# Switching_Regulator_LV_Board.net
KiCad netlist of a schematic drawn in Altium Designer
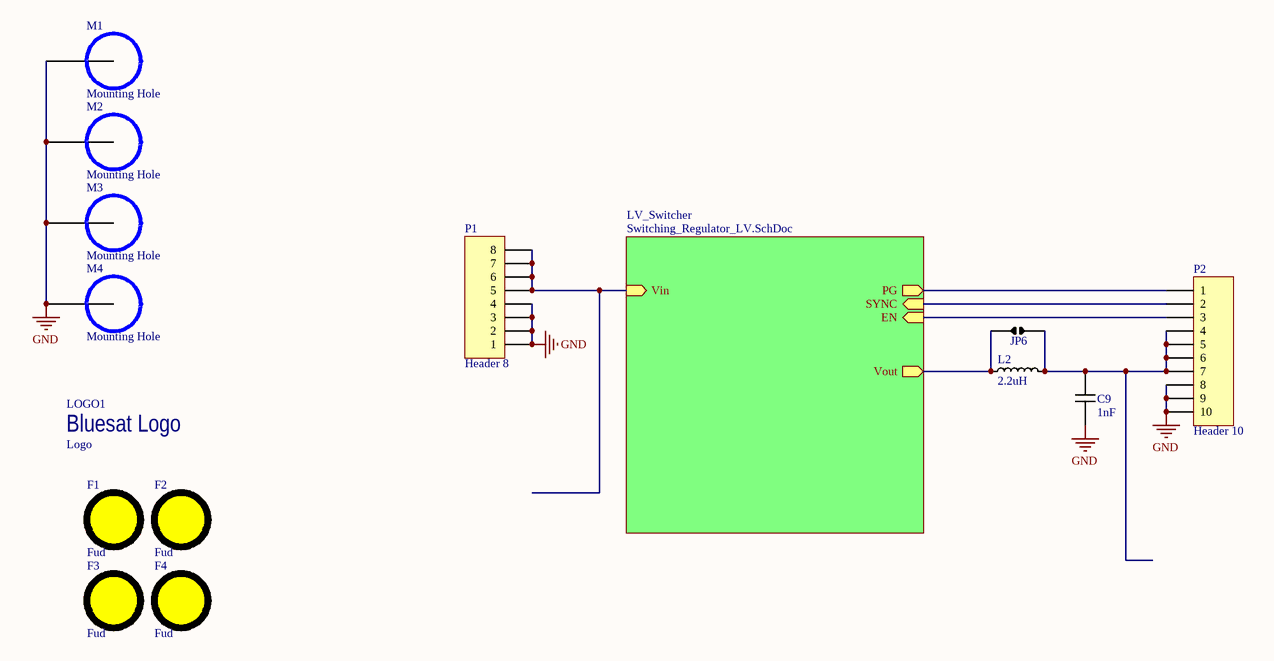
[diagram p0: Switching_Regulator_LV_Board.SchDoc]

(export (version "E")
  (design (tool "Eeschema 10.0.6"))
  (components
    (comp (ref "C9")
      (value "1nF")
      (footprint "0805 Cap")
      (description "0805 MLCC - X7R, 10%")
      (fields (field (name "Comment") "0805 Cap"))
      (libsource (lib "Schlib1") (part "0805 MLCC - X7R, 10%"))
    )
    (comp (ref "F1") (value "Fud") (footprint "FUd") (libsource (lib "Schlib1") (part "Fudicial")))
    (comp (ref "F2") (value "Fud") (footprint "FUd") (libsource (lib "Schlib1") (part "Fudicial")))
    (comp (ref "F3") (value "Fud") (footprint "FUd") (libsource (lib "Schlib1") (part "Fudicial")))
    (comp (ref "F4") (value "Fud") (footprint "FUd") (libsource (lib "Schlib1") (part "Fudicial")))
    (comp (ref "JP6")
      (value "Jumper")
      (footprint "Solder Jumper C")
      (description "Solder Bridge")
      (libsource (lib "Schlib1") (part "Solder Bridge"))
    )
    (comp (ref "L2")
      (value "2.2uH")
      (footprint "INDP4037X16N")
      (description "Inductor 4x4mm 2.2uH")
      (fields (field (name "Comment") "LQH44PN2R2MP0"))
      (libsource (lib "Schlib1") (part "LQH44PN2R2MP0"))
    )
    (comp (ref "LOGO1")
      (value "Logo")
      (footprint "BLUESAT_LOGO")
      (libsource (lib "Schlib1") (part "Bluesat Logo"))
    )
    (comp (ref "M1")
      (value "Mounting Hole")
      (footprint "Mounting_Hole")
      (libsource (lib "Schlib1") (part "Screw Hole"))
    )
    (comp (ref "M2")
      (value "Mounting Hole")
      (footprint "Mounting_Hole")
      (libsource (lib "Schlib1") (part "Screw Hole"))
    )
    (comp (ref "M3")
      (value "Mounting Hole")
      (footprint "Mounting_Hole")
      (libsource (lib "Schlib1") (part "Screw Hole"))
    )
    (comp (ref "M4")
      (value "Mounting Hole")
      (footprint "Mounting_Hole")
      (libsource (lib "Schlib1") (part "Screw Hole"))
    )
    (comp (ref "P1")
      (value "Header 8")
      (footprint "HDR1X8")
      (description "Header, 8-Pin")
      (fields (field (name "PUBLISHER") "Altium Limited"))
      (libsource (lib "Miscellaneous Connectors") (part "Header 8"))
    )
    (comp (ref "P2")
      (value "Header 10")
      (footprint "HDR1X10")
      (description "Header, 10-Pin")
      (fields (field (name "PUBLISHER") "Altium Limited"))
      (libsource (lib "Miscellaneous Connectors") (part "Header 10"))
    )
  )
  (nets
    (net (code "1") (name "/EN") (class "Default")
      (node (ref "P2") (pin "3") (pinfunction "3_3") (pintype "passive"))
    )
    (net (code "2") (name "/PG") (class "Default")
      (node (ref "P2") (pin "1") (pinfunction "1_1") (pintype "passive"))
    )
    (net (code "3") (name "/SYNC") (class "Default")
      (node (ref "P2") (pin "2") (pinfunction "2_2") (pintype "passive"))
    )
    (net (code "4") (name "/Vin") (class "Default")
      (node (ref "P1") (pin "5") (pinfunction "5_5") (pintype "passive"))
      (node (ref "P1") (pin "6") (pinfunction "6_6") (pintype "passive"))
      (node (ref "P1") (pin "7") (pinfunction "7_7") (pintype "passive"))
      (node (ref "P1") (pin "8") (pinfunction "8_8") (pintype "passive"))
    )
    (net (code "5") (name "/Vout") (class "Default")
      (node (ref "JP6") (pin "1") (pinfunction "1_1") (pintype "passive"))
      (node (ref "L2") (pin "1") (pinfunction "1_1") (pintype "passive"))
    )
    (net (code "6") (name "GND") (class "Default")
      (node (ref "C9") (pin "1") (pinfunction "1_1") (pintype "passive"))
      (node (ref "M1") (pin "1") (pinfunction "SH_1") (pintype "passive"))
      (node (ref "M2") (pin "1") (pinfunction "SH_1") (pintype "passive"))
      (node (ref "M3") (pin "1") (pinfunction "SH_1") (pintype "passive"))
      (node (ref "M4") (pin "1") (pinfunction "SH_1") (pintype "passive"))
      (node (ref "P1") (pin "1") (pinfunction "1_1") (pintype "passive"))
      (node (ref "P1") (pin "2") (pinfunction "2_2") (pintype "passive"))
      (node (ref "P1") (pin "3") (pinfunction "3_3") (pintype "passive"))
      (node (ref "P1") (pin "4") (pinfunction "4_4") (pintype "passive"))
      (node (ref "P2") (pin "10") (pinfunction "10_10") (pintype "passive"))
      (node (ref "P2") (pin "8") (pinfunction "8_8") (pintype "passive"))
      (node (ref "P2") (pin "9") (pinfunction "9_9") (pintype "passive"))
    )
    (net (code "7") (name "Net-(C9-Pad2)") (class "Default")
      (node (ref "C9") (pin "2") (pinfunction "2_2") (pintype "passive"))
      (node (ref "JP6") (pin "2") (pinfunction "2_2") (pintype "passive"))
      (node (ref "L2") (pin "2") (pinfunction "2_2") (pintype "passive"))
      (node (ref "P2") (pin "4") (pinfunction "4_4") (pintype "passive"))
      (node (ref "P2") (pin "5") (pinfunction "5_5") (pintype "passive"))
      (node (ref "P2") (pin "6") (pinfunction "6_6") (pintype "passive"))
      (node (ref "P2") (pin "7") (pinfunction "7_7") (pintype "passive"))
    )
  )
)
